# inAmp.net
KiCad netlist of a schematic drawn in Altium Designer
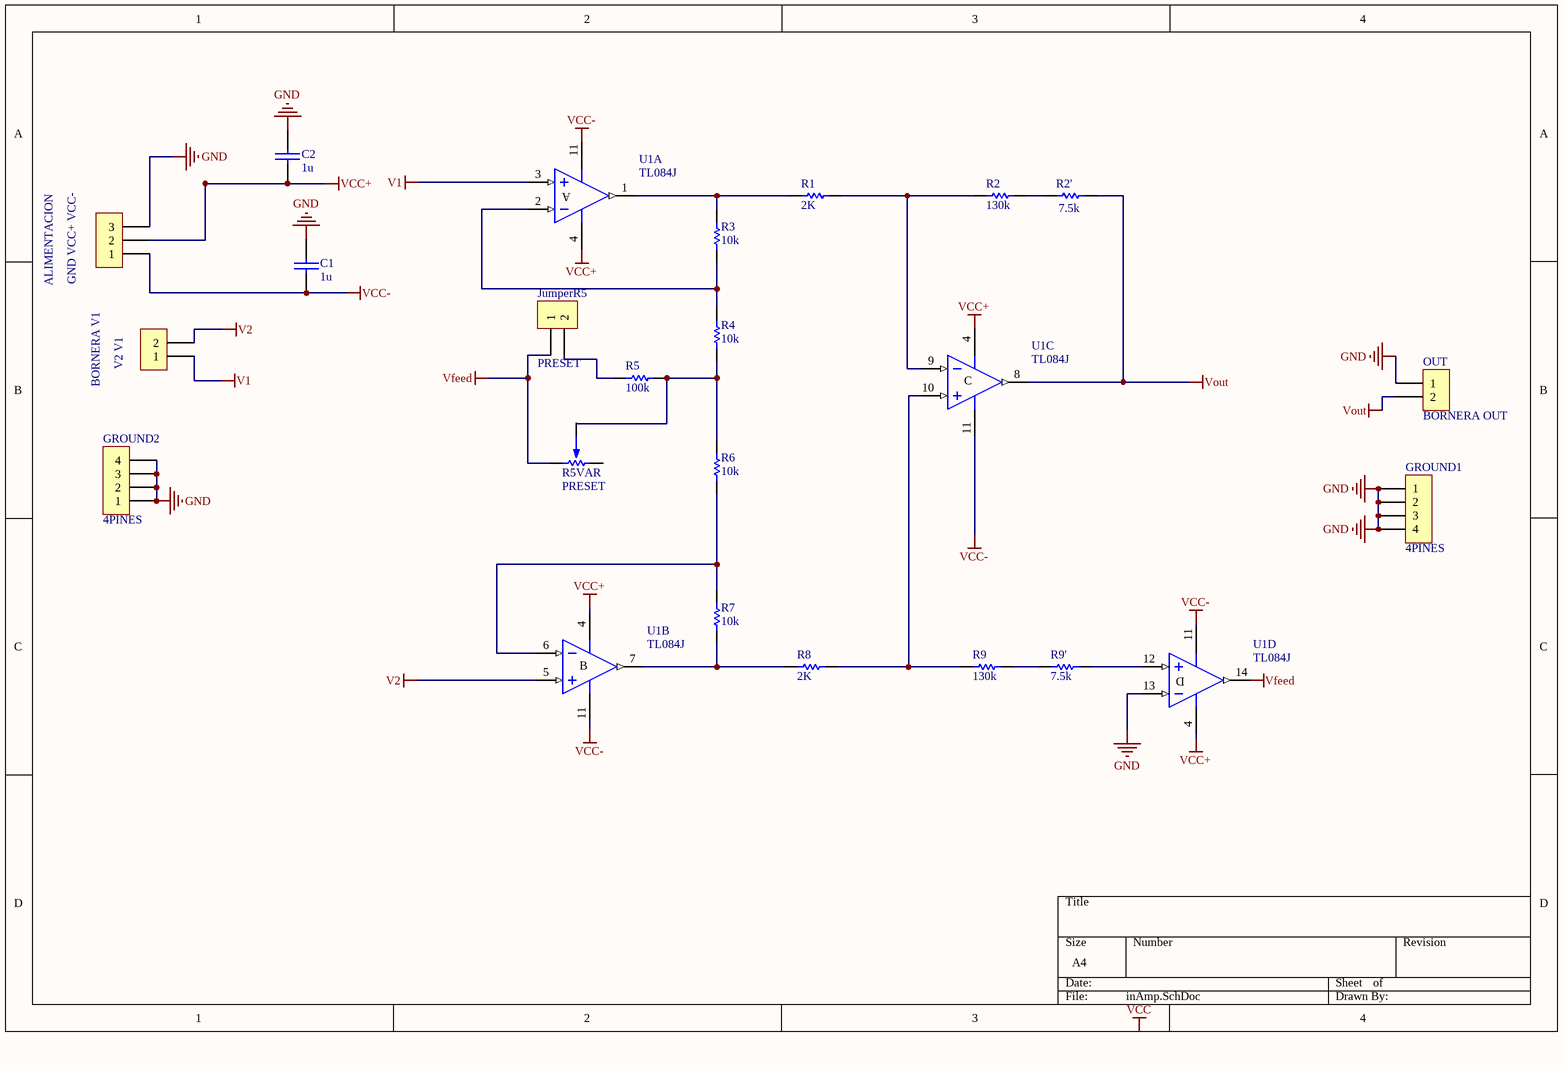
[diagram p0: inAmp.SchDoc]

(export (version "E")
  (design (tool "Eeschema 10.0.6"))
  (components
    (comp (ref "C1") (value "1u") (footprint "0805") (libsource (lib "LIBEBAL") (part "CAP")))
    (comp (ref "C2") (value "1u") (footprint "0805") (libsource (lib "LIBEBAL") (part "CAP")))
    (comp (ref "GND VCC+ VCC-")
      (value "ALIMENTACION")
      (footprint "BORNERA3")
      (libsource (lib "LIBEBAL Tobi") (part "BORNERA 3"))
    )
    (comp (ref "GROUND1") (value "4PINES") (footprint "SIP4") (libsource (lib "") (part "CON4_1")))
    (comp (ref "GROUND2") (value "4PINES") (footprint "SIP4") (libsource (lib "LIBEBAL") (part "CON4")))
    (comp (ref "JumperR5") (value "PRESET") (footprint "SIP2") (libsource (lib "LIBEBAL") (part "CON2")))
    (comp (ref "OUT")
      (value "BORNERA OUT")
      (footprint "BORNERA2")
      (libsource (lib "LIBEBAL Tobi") (part "BORNERA 2"))
    )
    (comp (ref "R1") (value "2K") (footprint "0805") (libsource (lib "LIBEBAL") (part "RES")))
    (comp (ref "R2") (value "130k") (footprint "0805") (libsource (lib "LIBEBAL") (part "RES")))
    (comp (ref "R2'") (value "7.5k") (footprint "0805") (libsource (lib "LIBEBAL Tobi") (part "RES")))
    (comp (ref "R3") (value "10k") (footprint "0805") (libsource (lib "LIBEBAL") (part "RES")))
    (comp (ref "R4") (value "10k") (footprint "0805") (libsource (lib "LIBEBAL") (part "RES")))
    (comp (ref "R5") (value "100k") (footprint "0805") (libsource (lib "LIBEBAL") (part "RES")))
    (comp (ref "R5VAR")
      (value "PRESET")
      (footprint "PRESET V")
      (libsource (lib "LIBEBAL Tobi") (part "PRESET"))
    )
    (comp (ref "R6") (value "10k") (footprint "0805") (libsource (lib "LIBEBAL") (part "RES")))
    (comp (ref "R7") (value "10k") (footprint "0805") (libsource (lib "LIBEBAL") (part "RES")))
    (comp (ref "R8") (value "2K") (footprint "0805") (libsource (lib "LIBEBAL") (part "RES")))
    (comp (ref "R9") (value "130k") (footprint "0805") (libsource (lib "LIBEBAL") (part "RES")))
    (comp (ref "R9'") (value "7.5k") (footprint "0805") (libsource (lib "LIBEBAL Tobi") (part "RES")))
    (comp (ref "U1")
      (value "TL084J")
      (footprint "J014")
      (description "JFET-Input Operational Amplifier")
      (fields (field (name "PUBLISHER") "Altium Limited"))
      (libsource (lib "TI Operational Amplifier") (part "TL084J"))
    )
    (comp (ref "V2 V1") (value "BORNERA V1") (footprint "BORNERA2") (libsource (lib "") (part "BORNERA 2_1")))
  )
  (nets
    (net (code "1") (name "GND") (class "Default")
      (node (ref "C1") (pin "1") (pinfunction "1_1") (pintype "passive"))
      (node (ref "C2") (pin "1") (pinfunction "1_1") (pintype "passive"))
      (node (ref "GND VCC+ VCC-") (pin "3") (pinfunction "3_3") (pintype "passive"))
      (node (ref "GROUND1") (pin "1") (pinfunction "1_1") (pintype "passive"))
      (node (ref "GROUND1") (pin "2") (pinfunction "2_2") (pintype "passive"))
      (node (ref "GROUND1") (pin "3") (pinfunction "3_3") (pintype "passive"))
      (node (ref "GROUND1") (pin "4") (pinfunction "4_4") (pintype "passive"))
      (node (ref "GROUND2") (pin "1") (pinfunction "1_1") (pintype "passive"))
      (node (ref "GROUND2") (pin "2") (pinfunction "2_2") (pintype "passive"))
      (node (ref "GROUND2") (pin "3") (pinfunction "3_3") (pintype "passive"))
      (node (ref "GROUND2") (pin "4") (pinfunction "4_4") (pintype "passive"))
      (node (ref "OUT") (pin "1") (pinfunction "1_1") (pintype "passive"))
      (node (ref "U1") (pin "13") (pinfunction "IN-_13") (pintype "input"))
    )
    (net (code "2") (name "Net-(JumperR5-Pad2)") (class "Default")
      (node (ref "JumperR5") (pin "2") (pinfunction "2_2") (pintype "passive"))
      (node (ref "R5") (pin "2") (pinfunction "2_2") (pintype "passive"))
    )
    (net (code "3") (name "Net-(R2'-Pad1)") (class "Default")
      (node (ref "R2") (pin "1") (pinfunction "1_1") (pintype "passive"))
      (node (ref "R2'") (pin "1") (pinfunction "1_1") (pintype "passive"))
    )
    (net (code "4") (name "Net-(R4-Pad1)") (class "Default")
      (node (ref "R4") (pin "1") (pinfunction "1_1") (pintype "passive"))
      (node (ref "R5") (pin "1") (pinfunction "1_1") (pintype "passive"))
      (node (ref "R5VAR") (pin "2") (pinfunction "2_2") (pintype "passive"))
      (node (ref "R6") (pin "2") (pinfunction "2_2") (pintype "passive"))
    )
    (net (code "5") (name "Net-(R9'-Pad1)") (class "Default")
      (node (ref "R9") (pin "1") (pinfunction "1_1") (pintype "passive"))
      (node (ref "R9'") (pin "1") (pinfunction "1_1") (pintype "passive"))
    )
    (net (code "6") (name "Net-(U1A-IN-)") (class "Default")
      (node (ref "R3") (pin "1") (pinfunction "1_1") (pintype "passive"))
      (node (ref "R4") (pin "2") (pinfunction "2_2") (pintype "passive"))
      (node (ref "U1") (pin "2") (pinfunction "IN-_2") (pintype "input"))
    )
    (net (code "7") (name "Net-(U1A-OUT)") (class "Default")
      (node (ref "R1") (pin "2") (pinfunction "2_2") (pintype "passive"))
      (node (ref "R3") (pin "2") (pinfunction "2_2") (pintype "passive"))
      (node (ref "U1") (pin "1") (pinfunction "OUT_1") (pintype "output"))
    )
    (net (code "8") (name "Net-(U1B-IN-)") (class "Default")
      (node (ref "R6") (pin "1") (pinfunction "1_1") (pintype "passive"))
      (node (ref "R7") (pin "2") (pinfunction "2_2") (pintype "passive"))
      (node (ref "U1") (pin "6") (pinfunction "IN-_6") (pintype "input"))
    )
    (net (code "9") (name "Net-(U1B-OUT)") (class "Default")
      (node (ref "R7") (pin "1") (pinfunction "1_1") (pintype "passive"))
      (node (ref "R8") (pin "2") (pinfunction "2_2") (pintype "passive"))
      (node (ref "U1") (pin "7") (pinfunction "OUT_7") (pintype "output"))
    )
    (net (code "10") (name "Net-(U1C-IN+)") (class "Default")
      (node (ref "R8") (pin "1") (pinfunction "1_1") (pintype "passive"))
      (node (ref "R9") (pin "2") (pinfunction "2_2") (pintype "passive"))
      (node (ref "U1") (pin "10") (pinfunction "IN+_10") (pintype "input"))
    )
    (net (code "11") (name "Net-(U1C-IN-)") (class "Default")
      (node (ref "R1") (pin "1") (pinfunction "1_1") (pintype "passive"))
      (node (ref "R2") (pin "2") (pinfunction "2_2") (pintype "passive"))
      (node (ref "U1") (pin "9") (pinfunction "IN-_9") (pintype "input"))
    )
    (net (code "12") (name "Net-(U1D-IN+)") (class "Default")
      (node (ref "R9'") (pin "2") (pinfunction "2_2") (pintype "passive"))
      (node (ref "U1") (pin "12") (pinfunction "IN+_12") (pintype "input"))
    )
    (net (code "13") (name "V1") (class "Default")
      (node (ref "U1") (pin "3") (pinfunction "IN+_3") (pintype "input"))
      (node (ref "V2 V1") (pin "1") (pinfunction "1_1") (pintype "passive"))
    )
    (net (code "14") (name "V2") (class "Default")
      (node (ref "U1") (pin "5") (pinfunction "IN+_5") (pintype "input"))
      (node (ref "V2 V1") (pin "2") (pinfunction "2_2") (pintype "passive"))
    )
    (net (code "16") (name "VCC+") (class "Default")
      (node (ref "C2") (pin "2") (pinfunction "2_2") (pintype "passive"))
      (node (ref "GND VCC+ VCC-") (pin "2") (pinfunction "2_2") (pintype "passive"))
      (node (ref "U1") (pin "4") (pinfunction "V+_4") (pintype "power_in"))
    )
    (net (code "17") (name "VCC-") (class "Default")
      (node (ref "C1") (pin "2") (pinfunction "2_2") (pintype "passive"))
      (node (ref "GND VCC+ VCC-") (pin "1") (pinfunction "1_1") (pintype "passive"))
      (node (ref "U1") (pin "11") (pinfunction "V-_11") (pintype "power_in"))
    )
    (net (code "18") (name "Vfeed") (class "Default")
      (node (ref "JumperR5") (pin "1") (pinfunction "1_1") (pintype "passive"))
      (node (ref "R5VAR") (pin "1") (pinfunction "1_1") (pintype "passive"))
      (node (ref "U1") (pin "14") (pinfunction "OUT_14") (pintype "output"))
    )
    (net (code "19") (name "Vout") (class "Default")
      (node (ref "OUT") (pin "2") (pinfunction "2_2") (pintype "passive"))
      (node (ref "R2'") (pin "2") (pinfunction "2_2") (pintype "passive"))
      (node (ref "U1") (pin "8") (pinfunction "OUT_8") (pintype "output"))
    )
    (net (code "20") (name "unconnected-(R5VAR-Pad3)") (class "Default")
      (node (ref "R5VAR") (pin "3") (pinfunction "3_3") (pintype "passive"))
    )
  )
)
